# Teensy3_2_v2_peripherie.net
KiCad netlist of a schematic drawn in EAGLE
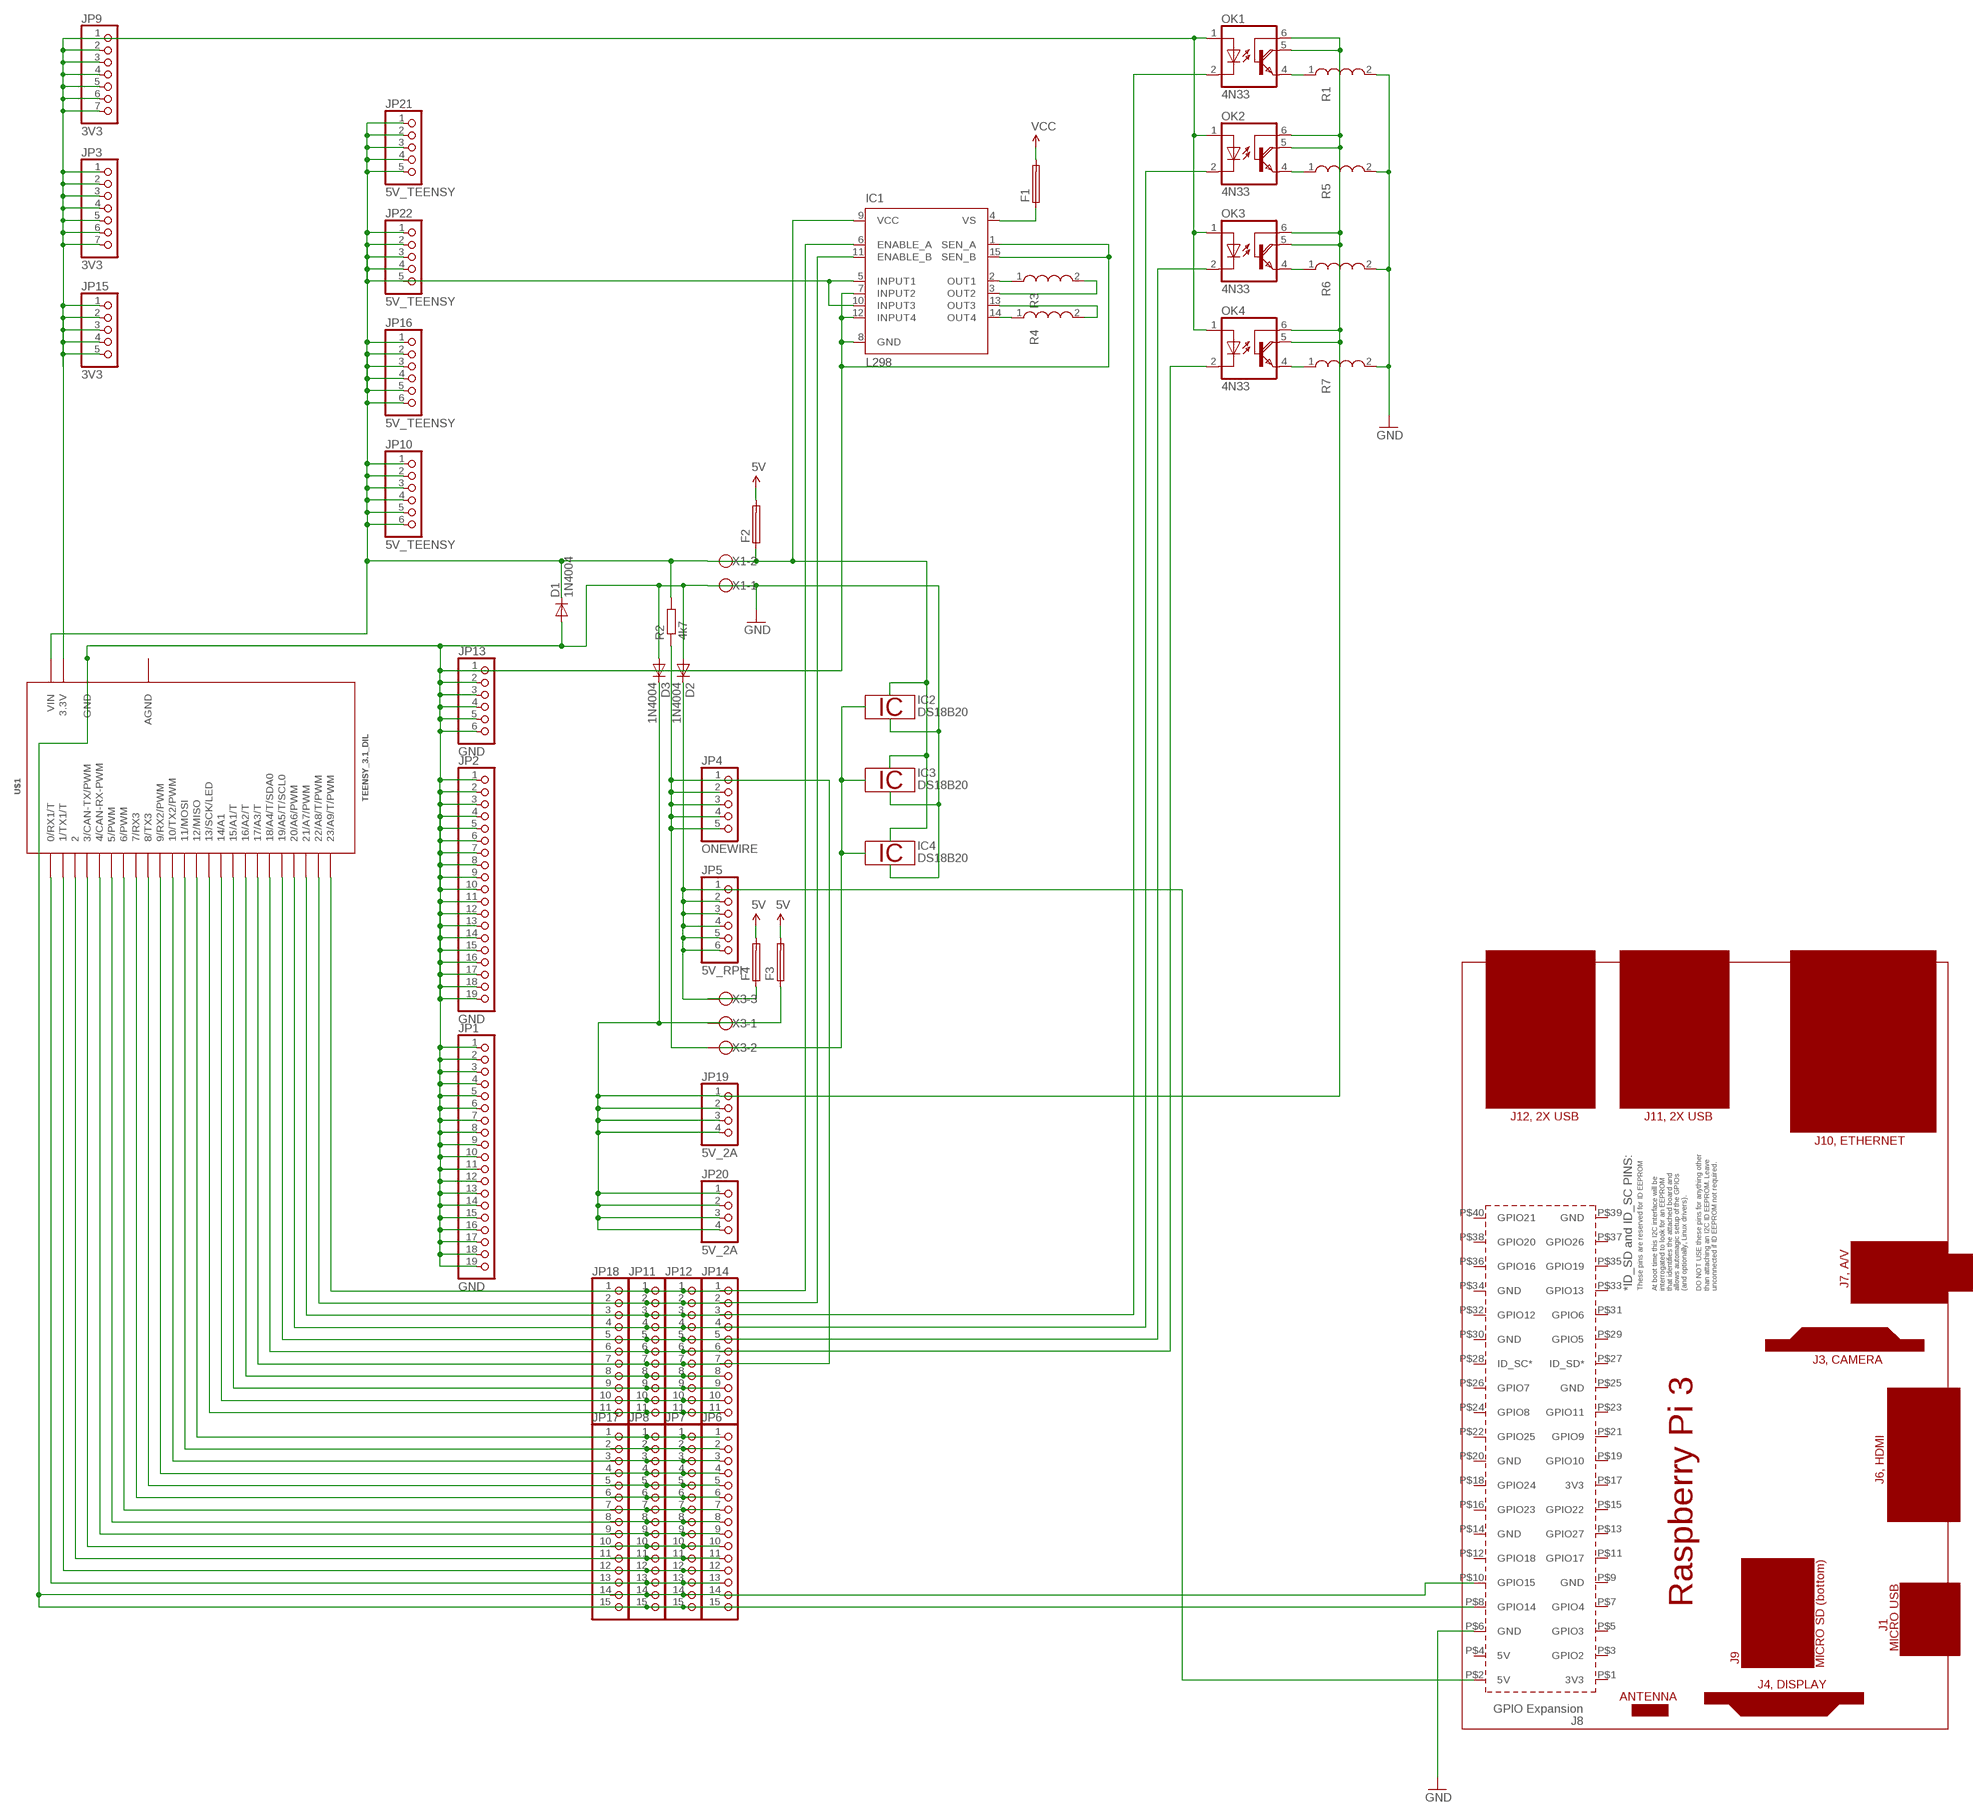
[diagram p0: schematic, sheet 1]

(export (version "E")
  (design (tool "Eeschema 10.0.6"))
  (components
    (comp (ref "D1")
      (value "1N4004")
      (footprint "eagle-import:DO41-10")
      (libsource (lib "eagle-import") (part "1N4004"))
    )
    (comp (ref "D2")
      (value "1N4004")
      (footprint "eagle-import:DO41-10")
      (libsource (lib "eagle-import") (part "1N4004"))
    )
    (comp (ref "D3")
      (value "1N4004")
      (footprint "eagle-import:DO41-10")
      (libsource (lib "eagle-import") (part "1N4004"))
    )
    (comp (ref "F1")
      (value "GSH15")
      (footprint "eagle-import:GSH15")
      (fields (field (name "MPN") "64900001039"))
      (libsource (lib "eagle-import") (part "GSH15"))
    )
    (comp (ref "F2")
      (value "GSH15")
      (footprint "eagle-import:GSH15")
      (fields (field (name "MPN") "64900001039"))
      (libsource (lib "eagle-import") (part "GSH15"))
    )
    (comp (ref "F3")
      (value "GSH15")
      (footprint "eagle-import:GSH15")
      (fields (field (name "MPN") "64900001039"))
      (libsource (lib "eagle-import") (part "GSH15"))
    )
    (comp (ref "F4")
      (value "GSH15")
      (footprint "eagle-import:GSH15")
      (fields (field (name "MPN") "64900001039"))
      (libsource (lib "eagle-import") (part "GSH15"))
    )
    (comp (ref "IC1")
      (value "L298")
      (footprint "eagle-import:MULTIWATT-15")
      (fields (field (name "MPN") "L298N"))
      (libsource (lib "eagle-import") (part "L298"))
    )
    (comp (ref "IC2")
      (value "DS18B20")
      (footprint "eagle-import:TO92-")
      (libsource (lib "eagle-import") (part "DS18B20"))
    )
    (comp (ref "IC3")
      (value "DS18B20")
      (footprint "eagle-import:TO92-")
      (libsource (lib "eagle-import") (part "DS18B20"))
    )
    (comp (ref "IC4")
      (value "DS18B20")
      (footprint "eagle-import:TO92-")
      (libsource (lib "eagle-import") (part "DS18B20"))
    )
    (comp (ref "JP1")
      (value "GND")
      (footprint "eagle-import:1X19")
      (libsource (lib "eagle-import") (part "PINHD-1X19"))
    )
    (comp (ref "JP2")
      (value "GND")
      (footprint "eagle-import:1X19")
      (libsource (lib "eagle-import") (part "PINHD-1X19"))
    )
    (comp (ref "JP3")
      (value "3V3")
      (footprint "eagle-import:1X07")
      (libsource (lib "eagle-import") (part "PINHD-1X7"))
    )
    (comp (ref "JP4")
      (value "ONEWIRE")
      (footprint "eagle-import:1X05")
      (libsource (lib "eagle-import") (part "PINHD-1X5"))
    )
    (comp (ref "JP5")
      (value "5V_RPI")
      (footprint "eagle-import:1X06")
      (libsource (lib "eagle-import") (part "PINHD-1X6"))
    )
    (comp (ref "JP6")
      (value "PINHD-1X15")
      (footprint "eagle-import:1X15")
      (libsource (lib "eagle-import") (part "PINHD-1X15"))
    )
    (comp (ref "JP7")
      (value "PINHD-1X15")
      (footprint "eagle-import:1X15")
      (libsource (lib "eagle-import") (part "PINHD-1X15"))
    )
    (comp (ref "JP8")
      (value "PINHD-1X15")
      (footprint "eagle-import:1X15")
      (libsource (lib "eagle-import") (part "PINHD-1X15"))
    )
    (comp (ref "JP9")
      (value "3V3")
      (footprint "eagle-import:1X07")
      (libsource (lib "eagle-import") (part "PINHD-1X7"))
    )
    (comp (ref "JP10")
      (value "5V_TEENSY")
      (footprint "eagle-import:1X06")
      (libsource (lib "eagle-import") (part "PINHD-1X6"))
    )
    (comp (ref "JP11")
      (value "PINHD-1X11")
      (footprint "eagle-import:1X11")
      (libsource (lib "eagle-import") (part "PINHD-1X11"))
    )
    (comp (ref "JP12")
      (value "PINHD-1X11")
      (footprint "eagle-import:1X11")
      (libsource (lib "eagle-import") (part "PINHD-1X11"))
    )
    (comp (ref "JP13")
      (value "GND")
      (footprint "eagle-import:1X06")
      (libsource (lib "eagle-import") (part "PINHD-1X6"))
    )
    (comp (ref "JP14")
      (value "PINHD-1X11")
      (footprint "eagle-import:1X11")
      (libsource (lib "eagle-import") (part "PINHD-1X11"))
    )
    (comp (ref "JP15")
      (value "3V3")
      (footprint "eagle-import:1X05")
      (libsource (lib "eagle-import") (part "PINHD-1X5"))
    )
    (comp (ref "JP16")
      (value "5V_TEENSY")
      (footprint "eagle-import:1X06")
      (libsource (lib "eagle-import") (part "PINHD-1X6"))
    )
    (comp (ref "JP17")
      (value "PINHD-1X15")
      (footprint "eagle-import:1X15")
      (libsource (lib "eagle-import") (part "PINHD-1X15"))
    )
    (comp (ref "JP18")
      (value "PINHD-1X11")
      (footprint "eagle-import:1X11")
      (libsource (lib "eagle-import") (part "PINHD-1X11"))
    )
    (comp (ref "JP19")
      (value "5V_2A")
      (footprint "eagle-import:1X04")
      (libsource (lib "eagle-import") (part "PINHD-1X4"))
    )
    (comp (ref "JP20")
      (value "5V_2A")
      (footprint "eagle-import:1X04")
      (libsource (lib "eagle-import") (part "PINHD-1X4"))
    )
    (comp (ref "JP21")
      (value "5V_TEENSY")
      (footprint "eagle-import:1X05")
      (libsource (lib "eagle-import") (part "PINHD-1X5"))
    )
    (comp (ref "JP22")
      (value "5V_TEENSY")
      (footprint "eagle-import:1X05")
      (libsource (lib "eagle-import") (part "PINHD-1X5"))
    )
    (comp (ref "OK1")
      (value "4N33")
      (footprint "eagle-import:DIL06")
      (fields (field (name "MF") "VISHAY/TELEFUNKEN"))
      (libsource (lib "eagle-import") (part "4N33"))
    )
    (comp (ref "OK2")
      (value "4N33")
      (footprint "eagle-import:DIL06")
      (fields (field (name "MF") "VISHAY/TELEFUNKEN"))
      (libsource (lib "eagle-import") (part "4N33"))
    )
    (comp (ref "OK3")
      (value "4N33")
      (footprint "eagle-import:DIL06")
      (fields (field (name "MF") "VISHAY/TELEFUNKEN"))
      (libsource (lib "eagle-import") (part "4N33"))
    )
    (comp (ref "OK4")
      (value "4N33")
      (footprint "eagle-import:DIL06")
      (fields (field (name "MF") "VISHAY/TELEFUNKEN"))
      (libsource (lib "eagle-import") (part "4N33"))
    )
    (comp (ref "PCB1")
      (value "RPI3")
      (footprint "eagle-import:RPI3")
      (libsource (lib "eagle-import") (part "RPI3"))
    )
    (comp (ref "R1")
      (value "SPULE_ALTERNATIV")
      (footprint "eagle-import:SPULE")
      (libsource (lib "eagle-import") (part "SPULE_ALTERNATIV"))
    )
    (comp (ref "R2")
      (value "4k7")
      (footprint "eagle-import:0204_5")
      (libsource (lib "eagle-import") (part "R-EU_0204/5"))
    )
    (comp (ref "R3")
      (value "SPULE_ALTERNATIV")
      (footprint "eagle-import:SPULE")
      (libsource (lib "eagle-import") (part "SPULE_ALTERNATIV"))
    )
    (comp (ref "R4")
      (value "SPULE_ALTERNATIV")
      (footprint "eagle-import:SPULE")
      (libsource (lib "eagle-import") (part "SPULE_ALTERNATIV"))
    )
    (comp (ref "R5")
      (value "SPULE_ALTERNATIV")
      (footprint "eagle-import:SPULE")
      (libsource (lib "eagle-import") (part "SPULE_ALTERNATIV"))
    )
    (comp (ref "R6")
      (value "SPULE_ALTERNATIV")
      (footprint "eagle-import:SPULE")
      (libsource (lib "eagle-import") (part "SPULE_ALTERNATIV"))
    )
    (comp (ref "R7")
      (value "SPULE_ALTERNATIV")
      (footprint "eagle-import:SPULE")
      (libsource (lib "eagle-import") (part "SPULE_ALTERNATIV"))
    )
    (comp (ref "U$1")
      (value "TEENSY_3.1_DIL")
      (footprint "eagle-import:TEENSY3-DIL")
      (libsource (lib "eagle-import") (part "TEENSY_3.1_DIL"))
    )
    (comp (ref "X1")
      (value "W237-102")
      (footprint "eagle-import:W237-102")
      (fields (field (name "MPN") "237-102"))
      (libsource (lib "eagle-import") (part "W237-102"))
    )
    (comp (ref "X3")
      (value "W237-103")
      (footprint "eagle-import:W237-103")
      (fields (field (name "MPN") "237-103"))
      (libsource (lib "eagle-import") (part "W237-103"))
    )
  )
  (nets
    (net (code "1") (name "/AGND") (class "Default")
      (node (ref "U$1") (pin "AGND") (pinfunction "AGND_AGND") (pintype "power_in"))
    )
    (net (code "2") (name "5V") (class "Default")
      (node (ref "F2") (pin "2") (pinfunction "2_2") (pintype "passive"))
      (node (ref "F3") (pin "2") (pinfunction "2_2") (pintype "passive"))
      (node (ref "F4") (pin "2") (pinfunction "2_2") (pintype "passive"))
    )
    (net (code "3") (name "GND") (class "Default")
      (node (ref "D1") (pin "A") (pinfunction "A_A") (pintype "passive"))
      (node (ref "D2") (pin "A") (pinfunction "A_A") (pintype "passive"))
      (node (ref "D3") (pin "A") (pinfunction "A_A") (pintype "passive"))
      (node (ref "IC1") (pin "1") (pinfunction "SEN_A_1") (pintype "input"))
      (node (ref "IC1") (pin "12") (pinfunction "INPUT4_12") (pintype "input"))
      (node (ref "IC1") (pin "15") (pinfunction "SEN_B_15") (pintype "input"))
      (node (ref "IC1") (pin "7") (pinfunction "INPUT2_7") (pintype "input"))
      (node (ref "IC1") (pin "8") (pinfunction "GND_8") (pintype "power_in"))
      (node (ref "JP1") (pin "1") (pinfunction "1_1") (pintype "passive"))
      (node (ref "JP1") (pin "10") (pinfunction "10_10") (pintype "passive"))
      (node (ref "JP1") (pin "11") (pinfunction "11_11") (pintype "passive"))
      (node (ref "JP1") (pin "12") (pinfunction "12_12") (pintype "passive"))
      (node (ref "JP1") (pin "13") (pinfunction "13_13") (pintype "passive"))
      (node (ref "JP1") (pin "14") (pinfunction "14_14") (pintype "passive"))
      (node (ref "JP1") (pin "15") (pinfunction "15_15") (pintype "passive"))
      (node (ref "JP1") (pin "16") (pinfunction "16_16") (pintype "passive"))
      (node (ref "JP1") (pin "17") (pinfunction "17_17") (pintype "passive"))
      (node (ref "JP1") (pin "18") (pinfunction "18_18") (pintype "passive"))
      (node (ref "JP1") (pin "19") (pinfunction "19_19") (pintype "passive"))
      (node (ref "JP1") (pin "2") (pinfunction "2_2") (pintype "passive"))
      (node (ref "JP1") (pin "3") (pinfunction "3_3") (pintype "passive"))
      (node (ref "JP1") (pin "4") (pinfunction "4_4") (pintype "passive"))
      (node (ref "JP1") (pin "5") (pinfunction "5_5") (pintype "passive"))
      (node (ref "JP1") (pin "6") (pinfunction "6_6") (pintype "passive"))
      (node (ref "JP1") (pin "7") (pinfunction "7_7") (pintype "passive"))
      (node (ref "JP1") (pin "8") (pinfunction "8_8") (pintype "passive"))
      (node (ref "JP1") (pin "9") (pinfunction "9_9") (pintype "passive"))
      (node (ref "JP13") (pin "1") (pinfunction "1_1") (pintype "passive"))
      (node (ref "JP13") (pin "2") (pinfunction "2_2") (pintype "passive"))
      (node (ref "JP13") (pin "3") (pinfunction "3_3") (pintype "passive"))
      (node (ref "JP13") (pin "4") (pinfunction "4_4") (pintype "passive"))
      (node (ref "JP13") (pin "5") (pinfunction "5_5") (pintype "passive"))
      (node (ref "JP13") (pin "6") (pinfunction "6_6") (pintype "passive"))
      (node (ref "JP17") (pin "14") (pinfunction "14_14") (pintype "passive"))
      (node (ref "JP17") (pin "15") (pinfunction "15_15") (pintype "passive"))
      (node (ref "JP2") (pin "1") (pinfunction "1_1") (pintype "passive"))
      (node (ref "JP2") (pin "10") (pinfunction "10_10") (pintype "passive"))
      (node (ref "JP2") (pin "11") (pinfunction "11_11") (pintype "passive"))
      (node (ref "JP2") (pin "12") (pinfunction "12_12") (pintype "passive"))
      (node (ref "JP2") (pin "13") (pinfunction "13_13") (pintype "passive"))
      (node (ref "JP2") (pin "14") (pinfunction "14_14") (pintype "passive"))
      (node (ref "JP2") (pin "15") (pinfunction "15_15") (pintype "passive"))
      (node (ref "JP2") (pin "16") (pinfunction "16_16") (pintype "passive"))
      (node (ref "JP2") (pin "17") (pinfunction "17_17") (pintype "passive"))
      (node (ref "JP2") (pin "18") (pinfunction "18_18") (pintype "passive"))
      (node (ref "JP2") (pin "19") (pinfunction "19_19") (pintype "passive"))
      (node (ref "JP2") (pin "2") (pinfunction "2_2") (pintype "passive"))
      (node (ref "JP2") (pin "3") (pinfunction "3_3") (pintype "passive"))
      (node (ref "JP2") (pin "4") (pinfunction "4_4") (pintype "passive"))
      (node (ref "JP2") (pin "5") (pinfunction "5_5") (pintype "passive"))
      (node (ref "JP2") (pin "6") (pinfunction "6_6") (pintype "passive"))
      (node (ref "JP2") (pin "7") (pinfunction "7_7") (pintype "passive"))
      (node (ref "JP2") (pin "8") (pinfunction "8_8") (pintype "passive"))
      (node (ref "JP2") (pin "9") (pinfunction "9_9") (pintype "passive"))
      (node (ref "JP6") (pin "14") (pinfunction "14_14") (pintype "passive"))
      (node (ref "JP6") (pin "15") (pinfunction "15_15") (pintype "passive"))
      (node (ref "JP7") (pin "14") (pinfunction "14_14") (pintype "passive"))
      (node (ref "JP7") (pin "15") (pinfunction "15_15") (pintype "passive"))
      (node (ref "JP8") (pin "14") (pinfunction "14_14") (pintype "passive"))
      (node (ref "JP8") (pin "15") (pinfunction "15_15") (pintype "passive"))
      (node (ref "PCB1") (pin "P$10") (pinfunction "GPIO15_P$10") (pintype "bidirectional"))
      (node (ref "PCB1") (pin "P$6") (pinfunction "GND_P$6") (pintype "bidirectional"))
      (node (ref "PCB1") (pin "P$8") (pinfunction "GPIO14_P$8") (pintype "bidirectional"))
      (node (ref "R1") (pin "2") (pinfunction "2_2") (pintype "passive"))
      (node (ref "R5") (pin "2") (pinfunction "2_2") (pintype "passive"))
      (node (ref "R6") (pin "2") (pinfunction "2_2") (pintype "passive"))
      (node (ref "R7") (pin "2") (pinfunction "2_2") (pintype "passive"))
      (node (ref "U$1") (pin "GND") (pinfunction "GND_GND") (pintype "power_in"))
      (node (ref "X1") (pin "1") (pinfunction "KL_1") (pintype "passive"))
    )
    (net (code "4") (name "Net-(IC1-ENABLE_A)") (class "Default")
      (node (ref "IC1") (pin "6") (pinfunction "ENABLE_A_6") (pintype "input"))
      (node (ref "JP11") (pin "1") (pinfunction "1_1") (pintype "passive"))
      (node (ref "JP12") (pin "1") (pinfunction "1_1") (pintype "passive"))
      (node (ref "JP14") (pin "1") (pinfunction "1_1") (pintype "passive"))
      (node (ref "JP18") (pin "1") (pinfunction "1_1") (pintype "passive"))
      (node (ref "U$1") (pin "23/A9") (pinfunction "23/A9/T/PWM_23/A9") (pintype "bidirectional"))
    )
    (net (code "5") (name "Net-(IC1-ENABLE_B)") (class "Default")
      (node (ref "IC1") (pin "11") (pinfunction "ENABLE_B_11") (pintype "input"))
      (node (ref "JP11") (pin "2") (pinfunction "2_2") (pintype "passive"))
      (node (ref "JP12") (pin "2") (pinfunction "2_2") (pintype "passive"))
      (node (ref "JP14") (pin "2") (pinfunction "2_2") (pintype "passive"))
      (node (ref "JP18") (pin "2") (pinfunction "2_2") (pintype "passive"))
      (node (ref "U$1") (pin "22/A8") (pinfunction "22/A8/T/PWM_22/A8") (pintype "bidirectional"))
    )
    (net (code "6") (name "Net-(IC1-INPUT1)") (class "Default")
      (node (ref "D1") (pin "C") (pinfunction "C_C") (pintype "passive"))
      (node (ref "F2") (pin "1") (pinfunction "1_1") (pintype "passive"))
      (node (ref "IC1") (pin "10") (pinfunction "INPUT3_10") (pintype "input"))
      (node (ref "IC1") (pin "5") (pinfunction "INPUT1_5") (pintype "input"))
      (node (ref "IC1") (pin "9") (pinfunction "VCC_9") (pintype "power_in"))
      (node (ref "JP10") (pin "1") (pinfunction "1_1") (pintype "passive"))
      (node (ref "JP10") (pin "2") (pinfunction "2_2") (pintype "passive"))
      (node (ref "JP10") (pin "3") (pinfunction "3_3") (pintype "passive"))
      (node (ref "JP10") (pin "4") (pinfunction "4_4") (pintype "passive"))
      (node (ref "JP10") (pin "5") (pinfunction "5_5") (pintype "passive"))
      (node (ref "JP10") (pin "6") (pinfunction "6_6") (pintype "passive"))
      (node (ref "JP16") (pin "1") (pinfunction "1_1") (pintype "passive"))
      (node (ref "JP16") (pin "2") (pinfunction "2_2") (pintype "passive"))
      (node (ref "JP16") (pin "3") (pinfunction "3_3") (pintype "passive"))
      (node (ref "JP16") (pin "4") (pinfunction "4_4") (pintype "passive"))
      (node (ref "JP16") (pin "5") (pinfunction "5_5") (pintype "passive"))
      (node (ref "JP16") (pin "6") (pinfunction "6_6") (pintype "passive"))
      (node (ref "JP21") (pin "1") (pinfunction "1_1") (pintype "passive"))
      (node (ref "JP21") (pin "2") (pinfunction "2_2") (pintype "passive"))
      (node (ref "JP21") (pin "3") (pinfunction "3_3") (pintype "passive"))
      (node (ref "JP21") (pin "4") (pinfunction "4_4") (pintype "passive"))
      (node (ref "JP21") (pin "5") (pinfunction "5_5") (pintype "passive"))
      (node (ref "JP22") (pin "1") (pinfunction "1_1") (pintype "passive"))
      (node (ref "JP22") (pin "2") (pinfunction "2_2") (pintype "passive"))
      (node (ref "JP22") (pin "3") (pinfunction "3_3") (pintype "passive"))
      (node (ref "JP22") (pin "4") (pinfunction "4_4") (pintype "passive"))
      (node (ref "JP22") (pin "5") (pinfunction "5_5") (pintype "passive"))
      (node (ref "R2") (pin "2") (pinfunction "2_2") (pintype "passive"))
      (node (ref "U$1") (pin "VIN") (pinfunction "VIN_VIN") (pintype "power_in"))
      (node (ref "X1") (pin "2") (pinfunction "KL_2") (pintype "passive"))
    )
    (net (code "7") (name "Net-(IC1-OUT1)") (class "Default")
      (node (ref "IC1") (pin "2") (pinfunction "OUT1_2") (pintype "output"))
      (node (ref "R3") (pin "1") (pinfunction "1_1") (pintype "passive"))
    )
    (net (code "8") (name "Net-(IC1-OUT2)") (class "Default")
      (node (ref "IC1") (pin "3") (pinfunction "OUT2_3") (pintype "output"))
      (node (ref "R3") (pin "2") (pinfunction "2_2") (pintype "passive"))
    )
    (net (code "9") (name "Net-(IC1-OUT3)") (class "Default")
      (node (ref "IC1") (pin "13") (pinfunction "OUT3_13") (pintype "output"))
      (node (ref "R4") (pin "2") (pinfunction "2_2") (pintype "passive"))
    )
    (net (code "10") (name "Net-(IC1-OUT4)") (class "Default")
      (node (ref "IC1") (pin "14") (pinfunction "OUT4_14") (pintype "output"))
      (node (ref "R4") (pin "1") (pinfunction "1_1") (pintype "passive"))
    )
    (net (code "11") (name "Net-(IC1-VS)") (class "Default")
      (node (ref "F1") (pin "1") (pinfunction "1_1") (pintype "passive"))
      (node (ref "IC1") (pin "4") (pinfunction "VS_4") (pintype "power_in"))
    )
    (net (code "12") (name "Net-(JP17-Pad11)") (class "Default")
      (node (ref "JP17") (pin "11") (pinfunction "11_11") (pintype "passive"))
      (node (ref "JP6") (pin "11") (pinfunction "11_11") (pintype "passive"))
      (node (ref "JP7") (pin "11") (pinfunction "11_11") (pintype "passive"))
      (node (ref "JP8") (pin "11") (pinfunction "11_11") (pintype "passive"))
      (node (ref "U$1") (pin "2") (pinfunction "2_2") (pintype "bidirectional"))
    )
    (net (code "13") (name "Net-(OK1-A)") (class "Default")
      (node (ref "JP15") (pin "1") (pinfunction "1_1") (pintype "passive"))
      (node (ref "JP15") (pin "2") (pinfunction "2_2") (pintype "passive"))
      (node (ref "JP15") (pin "3") (pinfunction "3_3") (pintype "passive"))
      (node (ref "JP15") (pin "4") (pinfunction "4_4") (pintype "passive"))
      (node (ref "JP15") (pin "5") (pinfunction "5_5") (pintype "passive"))
      (node (ref "JP3") (pin "1") (pinfunction "1_1") (pintype "passive"))
      (node (ref "JP3") (pin "2") (pinfunction "2_2") (pintype "passive"))
      (node (ref "JP3") (pin "3") (pinfunction "3_3") (pintype "passive"))
      (node (ref "JP3") (pin "4") (pinfunction "4_4") (pintype "passive"))
      (node (ref "JP3") (pin "5") (pinfunction "5_5") (pintype "passive"))
      (node (ref "JP3") (pin "6") (pinfunction "6_6") (pintype "passive"))
      (node (ref "JP3") (pin "7") (pinfunction "7_7") (pintype "passive"))
      (node (ref "JP9") (pin "1") (pinfunction "1_1") (pintype "passive"))
      (node (ref "JP9") (pin "2") (pinfunction "2_2") (pintype "passive"))
      (node (ref "JP9") (pin "3") (pinfunction "3_3") (pintype "passive"))
      (node (ref "JP9") (pin "4") (pinfunction "4_4") (pintype "passive"))
      (node (ref "JP9") (pin "5") (pinfunction "5_5") (pintype "passive"))
      (node (ref "JP9") (pin "6") (pinfunction "6_6") (pintype "passive"))
      (node (ref "JP9") (pin "7") (pinfunction "7_7") (pintype "passive"))
      (node (ref "OK1") (pin "1") (pinfunction "A_1") (pintype "passive"))
      (node (ref "OK2") (pin "1") (pinfunction "A_1") (pintype "passive"))
      (node (ref "OK3") (pin "1") (pinfunction "A_1") (pintype "passive"))
      (node (ref "OK4") (pin "1") (pinfunction "A_1") (pintype "passive"))
      (node (ref "U$1") (pin "3.3V") (pinfunction "3.3V_3.3V") (pintype "power_in"))
    )
    (net (code "14") (name "Net-(OK1-B)") (class "Default")
      (node (ref "D3") (pin "C") (pinfunction "C_C") (pintype "passive"))
      (node (ref "F3") (pin "1") (pinfunction "1_1") (pintype "passive"))
      (node (ref "JP19") (pin "1") (pinfunction "1_1") (pintype "passive"))
      (node (ref "JP19") (pin "2") (pinfunction "2_2") (pintype "passive"))
      (node (ref "JP19") (pin "3") (pinfunction "3_3") (pintype "passive"))
      (node (ref "JP19") (pin "4") (pinfunction "4_4") (pintype "passive"))
      (node (ref "JP20") (pin "1") (pinfunction "1_1") (pintype "passive"))
      (node (ref "JP20") (pin "2") (pinfunction "2_2") (pintype "passive"))
      (node (ref "JP20") (pin "3") (pinfunction "3_3") (pintype "passive"))
      (node (ref "JP20") (pin "4") (pinfunction "4_4") (pintype "passive"))
      (node (ref "OK1") (pin "5") (pinfunction "COL_5") (pintype "passive"))
      (node (ref "OK1") (pin "6") (pinfunction "B_6") (pintype "passive"))
      (node (ref "OK2") (pin "5") (pinfunction "COL_5") (pintype "passive"))
      (node (ref "OK2") (pin "6") (pinfunction "B_6") (pintype "passive"))
      (node (ref "OK3") (pin "5") (pinfunction "COL_5") (pintype "passive"))
      (node (ref "OK3") (pin "6") (pinfunction "B_6") (pintype "passive"))
      (node (ref "OK4") (pin "5") (pinfunction "COL_5") (pintype "passive"))
      (node (ref "OK4") (pin "6") (pinfunction "B_6") (pintype "passive"))
      (node (ref "X3") (pin "1") (pinfunction "KL_1") (pintype "passive"))
    )
    (net (code "15") (name "Net-(OK1-C)") (class "Default")
      (node (ref "JP11") (pin "3") (pinfunction "3_3") (pintype "passive"))
      (node (ref "JP12") (pin "3") (pinfunction "3_3") (pintype "passive"))
      (node (ref "JP14") (pin "3") (pinfunction "3_3") (pintype "passive"))
      (node (ref "JP18") (pin "3") (pinfunction "3_3") (pintype "passive"))
      (node (ref "OK1") (pin "2") (pinfunction "C_2") (pintype "passive"))
      (node (ref "U$1") (pin "21/A7") (pinfunction "21/A7/PWM_21/A7") (pintype "bidirectional"))
    )
    (net (code "16") (name "Net-(OK1-E)") (class "Default")
      (node (ref "OK1") (pin "4") (pinfunction "E_4") (pintype "passive"))
      (node (ref "R1") (pin "1") (pinfunction "1_1") (pintype "passive"))
    )
    (net (code "17") (name "Net-(OK2-C)") (class "Default")
      (node (ref "JP11") (pin "4") (pinfunction "4_4") (pintype "passive"))
      (node (ref "JP12") (pin "4") (pinfunction "4_4") (pintype "passive"))
      (node (ref "JP14") (pin "4") (pinfunction "4_4") (pintype "passive"))
      (node (ref "JP18") (pin "4") (pinfunction "4_4") (pintype "passive"))
      (node (ref "OK2") (pin "2") (pinfunction "C_2") (pintype "passive"))
      (node (ref "U$1") (pin "20/A6") (pinfunction "20/A6/PWM_20/A6") (pintype "bidirectional"))
    )
    (net (code "18") (name "Net-(OK2-E)") (class "Default")
      (node (ref "OK2") (pin "4") (pinfunction "E_4") (pintype "passive"))
      (node (ref "R5") (pin "1") (pinfunction "1_1") (pintype "passive"))
    )
    (net (code "19") (name "Net-(OK3-C)") (class "Default")
      (node (ref "JP11") (pin "5") (pinfunction "5_5") (pintype "passive"))
      (node (ref "JP12") (pin "5") (pinfunction "5_5") (pintype "passive"))
      (node (ref "JP14") (pin "5") (pinfunction "5_5") (pintype "passive"))
      (node (ref "JP18") (pin "5") (pinfunction "5_5") (pintype "passive"))
      (node (ref "OK3") (pin "2") (pinfunction "C_2") (pintype "passive"))
      (node (ref "U$1") (pin "19/A5") (pinfunction "19/A5/T/SCL0_19/A5") (pintype "bidirectional"))
    )
    (net (code "20") (name "Net-(OK3-E)") (class "Default")
      (node (ref "OK3") (pin "4") (pinfunction "E_4") (pintype "passive"))
      (node (ref "R6") (pin "1") (pinfunction "1_1") (pintype "passive"))
    )
    (net (code "21") (name "Net-(OK4-C)") (class "Default")
      (node (ref "JP11") (pin "6") (pinfunction "6_6") (pintype "passive"))
      (node (ref "JP12") (pin "6") (pinfunction "6_6") (pintype "passive"))
      (node (ref "JP14") (pin "6") (pinfunction "6_6") (pintype "passive"))
      (node (ref "JP18") (pin "6") (pinfunction "6_6") (pintype "passive"))
      (node (ref "OK4") (pin "2") (pinfunction "C_2") (pintype "passive"))
      (node (ref "U$1") (pin "18/A4") (pinfunction "18/A4/T/SDA0_18/A4") (pintype "bidirectional"))
    )
    (net (code "22") (name "Net-(OK4-E)") (class "Default")
      (node (ref "OK4") (pin "4") (pinfunction "E_4") (pintype "passive"))
      (node (ref "R7") (pin "1") (pinfunction "1_1") (pintype "passive"))
    )
    (net (code "23") (name "Net-(U$1-0{slash}RX1{slash}T)") (class "Default")
      (node (ref "JP17") (pin "13") (pinfunction "13_13") (pintype "passive"))
      (node (ref "JP6") (pin "13") (pinfunction "13_13") (pintype "passive"))
      (node (ref "JP7") (pin "13") (pinfunction "13_13") (pintype "passive"))
      (node (ref "JP8") (pin "13") (pinfunction "13_13") (pintype "passive"))
      (node (ref "U$1") (pin "0") (pinfunction "0/RX1/T_0") (pintype "bidirectional"))
    )
    (net (code "24") (name "Net-(U$1-1{slash}TX1{slash}T)") (class "Default")
      (node (ref "JP17") (pin "12") (pinfunction "12_12") (pintype "passive"))
      (node (ref "JP6") (pin "12") (pinfunction "12_12") (pintype "passive"))
      (node (ref "JP7") (pin "12") (pinfunction "12_12") (pintype "passive"))
      (node (ref "JP8") (pin "12") (pinfunction "12_12") (pintype "passive"))
      (node (ref "U$1") (pin "1") (pinfunction "1/TX1/T_1") (pintype "bidirectional"))
    )
    (net (code "25") (name "Net-(U$1-3{slash}CAN-TX{slash}PWM)") (class "Default")
      (node (ref "JP17") (pin "10") (pinfunction "10_10") (pintype "passive"))
      (node (ref "JP6") (pin "10") (pinfunction "10_10") (pintype "passive"))
      (node (ref "JP7") (pin "10") (pinfunction "10_10") (pintype "passive"))
      (node (ref "JP8") (pin "10") (pinfunction "10_10") (pintype "passive"))
      (node (ref "U$1") (pin "3") (pinfunction "3/CAN-TX/PWM_3") (pintype "bidirectional"))
    )
    (net (code "26") (name "Net-(U$1-4{slash}CAN-RX-PWM)") (class "Default")
      (node (ref "JP17") (pin "9") (pinfunction "9_9") (pintype "passive"))
      (node (ref "JP6") (pin "9") (pinfunction "9_9") (pintype "passive"))
      (node (ref "JP7") (pin "9") (pinfunction "9_9") (pintype "passive"))
      (node (ref "JP8") (pin "9") (pinfunction "9_9") (pintype "passive"))
      (node (ref "U$1") (pin "4") (pinfunction "4/CAN-RX-PWM_4") (pintype "bidirectional"))
    )
    (net (code "27") (name "Net-(U$1-5{slash}PWM)") (class "Default")
      (node (ref "JP17") (pin "8") (pinfunction "8_8") (pintype "passive"))
      (node (ref "JP6") (pin "8") (pinfunction "8_8") (pintype "passive"))
      (node (ref "JP7") (pin "8") (pinfunction "8_8") (pintype "passive"))
      (node (ref "JP8") (pin "8") (pinfunction "8_8") (pintype "passive"))
      (node (ref "U$1") (pin "5") (pinfunction "5/PWM_5") (pintype "bidirectional"))
    )
    (net (code "28") (name "Net-(U$1-6{slash}PWM)") (class "Default")
      (node (ref "JP17") (pin "7") (pinfunction "7_7") (pintype "passive"))
      (node (ref "JP6") (pin "7") (pinfunction "7_7") (pintype "passive"))
      (node (ref "JP7") (pin "7") (pinfunction "7_7") (pintype "passive"))
      (node (ref "JP8") (pin "7") (pinfunction "7_7") (pintype "passive"))
      (node (ref "U$1") (pin "6") (pinfunction "6/PWM_6") (pintype "bidirectional"))
    )
    (net (code "29") (name "Net-(U$1-7{slash}RX3)") (class "Default")
      (node (ref "JP17") (pin "6") (pinfunction "6_6") (pintype "passive"))
      (node (ref "JP6") (pin "6") (pinfunction "6_6") (pintype "passive"))
      (node (ref "JP7") (pin "6") (pinfunction "6_6") (pintype "passive"))
      (node (ref "JP8") (pin "6") (pinfunction "6_6") (pintype "passive"))
      (node (ref "U$1") (pin "7") (pinfunction "7/RX3_7") (pintype "bidirectional"))
    )
    (net (code "30") (name "Net-(U$1-8{slash}TX3)") (class "Default")
      (node (ref "JP17") (pin "5") (pinfunction "5_5") (pintype "passive"))
      (node (ref "JP6") (pin "5") (pinfunction "5_5") (pintype "passive"))
      (node (ref "JP7") (pin "5") (pinfunction "5_5") (pintype "passive"))
      (node (ref "JP8") (pin "5") (pinfunction "5_5") (pintype "passive"))
      (node (ref "U$1") (pin "8") (pinfunction "8/TX3_8") (pintype "bidirectional"))
    )
    (net (code "31") (name "Net-(U$1-9{slash}RX2{slash}PWM)") (class "Default")
      (node (ref "JP17") (pin "4") (pinfunction "4_4") (pintype "passive"))
      (node (ref "JP6") (pin "4") (pinfunction "4_4") (pintype "passive"))
      (node (ref "JP7") (pin "4") (pinfunction "4_4") (pintype "passive"))
      (node (ref "JP8") (pin "4") (pinfunction "4_4") (pintype "passive"))
      (node (ref "U$1") (pin "9") (pinfunction "9/RX2/PWM_9") (pintype "bidirectional"))
    )
    (net (code "32") (name "Net-(U$1-10{slash}TX2{slash}PWM)") (class "Default")
      (node (ref "JP17") (pin "3") (pinfunction "3_3") (pintype "passive"))
      (node (ref "JP6") (pin "3") (pinfunction "3_3") (pintype "passive"))
      (node (ref "JP7") (pin "3") (pinfunction "3_3") (pintype "passive"))
      (node (ref "JP8") (pin "3") (pinfunction "3_3") (pintype "passive"))
      (node (ref "U$1") (pin "10") (pinfunction "10/TX2/PWM_10") (pintype "bidirectional"))
    )
    (net (code "33") (name "Net-(U$1-11{slash}MOSI)") (class "Default")
      (node (ref "JP17") (pin "2") (pinfunction "2_2") (pintype "passive"))
      (node (ref "JP6") (pin "2") (pinfunction "2_2") (pintype "passive"))
      (node (ref "JP7") (pin "2") (pinfunction "2_2") (pintype "passive"))
      (node (ref "JP8") (pin "2") (pinfunction "2_2") (pintype "passive"))
      (node (ref "U$1") (pin "11") (pinfunction "11/MOSI_11") (pintype "bidirectional"))
    )
    (net (code "34") (name "Net-(U$1-12{slash}MISO)") (class "Default")
      (node (ref "JP17") (pin "1") (pinfunction "1_1") (pintype "passive"))
      (node (ref "JP6") (pin "1") (pinfunction "1_1") (pintype "passive"))
      (node (ref "JP7") (pin "1") (pinfunction "1_1") (pintype "passive"))
      (node (ref "JP8") (pin "1") (pinfunction "1_1") (pintype "passive"))
      (node (ref "U$1") (pin "12") (pinfunction "12/MISO_12") (pintype "bidirectional"))
    )
    (net (code "35") (name "Net-(U$1-13{slash}SCK{slash}LED)") (class "Default")
      (node (ref "JP11") (pin "11") (pinfunction "11_11") (pintype "passive"))
      (node (ref "JP12") (pin "11") (pinfunction "11_11") (pintype "passive"))
      (node (ref "JP14") (pin "11") (pinfunction "11_11") (pintype "passive"))
      (node (ref "JP18") (pin "11") (pinfunction "11_11") (pintype "passive"))
      (node (ref "U$1") (pin "13") (pinfunction "13/SCK/LED_13") (pintype "bidirectional"))
    )
    (net (code "36") (name "Net-(U$1-14{slash}A1)") (class "Default")
      (node (ref "JP11") (pin "10") (pinfunction "10_10") (pintype "passive"))
      (node (ref "JP12") (pin "10") (pinfunction "10_10") (pintype "passive"))
      (node (ref "JP14") (pin "10") (pinfunction "10_10") (pintype "passive"))
      (node (ref "JP18") (pin "10") (pinfunction "10_10") (pintype "passive"))
      (node (ref "U$1") (pin "14/A0") (pinfunction "14/A1_14/A0") (pintype "bidirectional"))
    )
    (net (code "37") (name "Net-(U$1-15{slash}A1{slash}T)") (class "Default")
      (node (ref "JP11") (pin "9") (pinfunction "9_9") (pintype "passive"))
      (node (ref "JP12") (pin "9") (pinfunction "9_9") (pintype "passive"))
      (node (ref "JP14") (pin "9") (pinfunction "9_9") (pintype "passive"))
      (node (ref "JP18") (pin "9") (pinfunction "9_9") (pintype "passive"))
      (node (ref "U$1") (pin "15/A1") (pinfunction "15/A1/T_15/A1") (pintype "bidirectional"))
    )
    (net (code "38") (name "Net-(U$1-16{slash}A2{slash}T)") (class "Default")
      (node (ref "JP11") (pin "8") (pinfunction "8_8") (pintype "passive"))
      (node (ref "JP12") (pin "8") (pinfunction "8_8") (pintype "passive"))
      (node (ref "JP14") (pin "8") (pinfunction "8_8") (pintype "passive"))
      (node (ref "JP18") (pin "8") (pinfunction "8_8") (pintype "passive"))
      (node (ref "U$1") (pin "16/A2") (pinfunction "16/A2/T_16/A2") (pintype "bidirectional"))
    )
    (net (code "39") (name "Net-(U$1-17{slash}A3{slash}T)") (class "Default")
      (node (ref "JP11") (pin "7") (pinfunction "7_7") (pintype "passive"))
      (node (ref "JP12") (pin "7") (pinfunction "7_7") (pintype "passive"))
      (node (ref "JP14") (pin "7") (pinfunction "7_7") (pintype "passive"))
      (node (ref "JP18") (pin "7") (pinfunction "7_7") (pintype "passive"))
      (node (ref "JP4") (pin "1") (pinfunction "1_1") (pintype "passive"))
      (node (ref "JP4") (pin "2") (pinfunction "2_2") (pintype "passive"))
      (node (ref "JP4") (pin "3") (pinfunction "3_3") (pintype "passive"))
      (node (ref "JP4") (pin "4") (pinfunction "4_4") (pintype "passive"))
      (node (ref "JP4") (pin "5") (pinfunction "5_5") (pintype "passive"))
      (node (ref "R2") (pin "1") (pinfunction "1_1") (pintype "passive"))
      (node (ref "U$1") (pin "17/A3") (pinfunction "17/A3/T_17/A3") (pintype "bidirectional"))
      (node (ref "X3") (pin "2") (pinfunction "KL_2") (pintype "passive"))
    )
    (net (code "40") (name "Net-(X3C-KL)") (class "Default")
      (node (ref "D2") (pin "C") (pinfunction "C_C") (pintype "passive"))
      (node (ref "F4") (pin "1") (pinfunction "1_1") (pintype "passive"))
      (node (ref "JP5") (pin "1") (pinfunction "1_1") (pintype "passive"))
      (node (ref "JP5") (pin "2") (pinfunction "2_2") (pintype "passive"))
      (node (ref "JP5") (pin "3") (pinfunction "3_3") (pintype "passive"))
      (node (ref "JP5") (pin "4") (pinfunction "4_4") (pintype "passive"))
      (node (ref "JP5") (pin "5") (pinfunction "5_5") (pintype "passive"))
      (node (ref "JP5") (pin "6") (pinfunction "6_6") (pintype "passive"))
      (node (ref "PCB1") (pin "P$2") (pinfunction "5V_P$2") (pintype "bidirectional"))
      (node (ref "X3") (pin "3") (pinfunction "KL_3") (pintype "passive"))
    )
    (net (code "41") (name "VCC") (class "Default")
      (node (ref "F1") (pin "2") (pinfunction "2_2") (pintype "passive"))
    )
    (net (code "42") (name "unconnected-(PCB1-3V3-PadP$1)") (class "Default")
      (node (ref "PCB1") (pin "P$1") (pinfunction "3V3_P$1") (pintype "bidirectional"))
    )
    (net (code "43") (name "unconnected-(PCB1-3V3-PadP$17)") (class "Default")
      (node (ref "PCB1") (pin "P$17") (pinfunction "3V3_P$17") (pintype "bidirectional"))
    )
    (net (code "44") (name "unconnected-(PCB1-5V-PadP$4)") (class "Default")
      (node (ref "PCB1") (pin "P$4") (pinfunction "5V_P$4") (pintype "bidirectional"))
    )
    (net (code "45") (name "unconnected-(PCB1-GND-PadP$9)") (class "Default")
      (node (ref "PCB1") (pin "P$9") (pinfunction "GND_P$9") (pintype "bidirectional"))
    )
    (net (code "46") (name "unconnected-(PCB1-GND-PadP$14)") (class "Default")
      (node (ref "PCB1") (pin "P$14") (pinfunction "GND_P$14") (pintype "bidirectional"))
    )
    (net (code "47") (name "unconnected-(PCB1-GND-PadP$20)") (class "Default")
      (node (ref "PCB1") (pin "P$20") (pinfunction "GND_P$20") (pintype "bidirectional"))
    )
    (net (code "48") (name "unconnected-(PCB1-GND-PadP$25)") (class "Default")
      (node (ref "PCB1") (pin "P$25") (pinfunction "GND_P$25") (pintype "bidirectional"))
    )
    (net (code "49") (name "unconnected-(PCB1-GND-PadP$30)") (class "Default")
      (node (ref "PCB1") (pin "P$30") (pinfunction "GND_P$30") (pintype "bidirectional"))
    )
    (net (code "50") (name "unconnected-(PCB1-GND-PadP$34)") (class "Default")
      (node (ref "PCB1") (pin "P$34") (pinfunction "GND_P$34") (pintype "bidirectional"))
    )
    (net (code "51") (name "unconnected-(PCB1-GND-PadP$39)") (class "Default")
      (node (ref "PCB1") (pin "P$39") (pinfunction "GND_P$39") (pintype "bidirectional"))
    )
    (net (code "52") (name "unconnected-(PCB1-GPIO2-PadP$3)") (class "Default")
      (node (ref "PCB1") (pin "P$3") (pinfunction "GPIO2_P$3") (pintype "bidirectional"))
    )
    (net (code "53") (name "unconnected-(PCB1-GPIO3-PadP$5)") (class "Default")
      (node (ref "PCB1") (pin "P$5") (pinfunction "GPIO3_P$5") (pintype "bidirectional"))
    )
    (net (code "54") (name "unconnected-(PCB1-GPIO4-PadP$7)") (class "Default")
      (node (ref "PCB1") (pin "P$7") (pinfunction "GPIO4_P$7") (pintype "bidirectional"))
    )
    (net (code "55") (name "unconnected-(PCB1-GPIO5-PadP$29)") (class "Default")
      (node (ref "PCB1") (pin "P$29") (pinfunction "GPIO5_P$29") (pintype "bidirectional"))
    )
    (net (code "56") (name "unconnected-(PCB1-GPIO6-PadP$31)") (class "Default")
      (node (ref "PCB1") (pin "P$31") (pinfunction "GPIO6_P$31") (pintype "bidirectional"))
    )
    (net (code "57") (name "unconnected-(PCB1-GPIO7-PadP$26)") (class "Default")
      (node (ref "PCB1") (pin "P$26") (pinfunction "GPIO7_P$26") (pintype "bidirectional"))
    )
    (net (code "58") (name "unconnected-(PCB1-GPIO8-PadP$24)") (class "Default")
      (node (ref "PCB1") (pin "P$24") (pinfunction "GPIO8_P$24") (pintype "bidirectional"))
    )
    (net (code "59") (name "unconnected-(PCB1-GPIO9-PadP$21)") (class "Default")
      (node (ref "PCB1") (pin "P$21") (pinfunction "GPIO9_P$21") (pintype "bidirectional"))
    )
    (net (code "60") (name "unconnected-(PCB1-GPIO10-PadP$19)") (class "Default")
      (node (ref "PCB1") (pin "P$19") (pinfunction "GPIO10_P$19") (pintype "bidirectional"))
    )
    (net (code "61") (name "unconnected-(PCB1-GPIO11-PadP$23)") (class "Default")
      (node (ref "PCB1") (pin "P$23") (pinfunction "GPIO11_P$23") (pintype "bidirectional"))
    )
    (net (code "62") (name "unconnected-(PCB1-GPIO12-PadP$32)") (class "Default")
      (node (ref "PCB1") (pin "P$32") (pinfunction "GPIO12_P$32") (pintype "bidirectional"))
    )
    (net (code "63") (name "unconnected-(PCB1-GPIO13-PadP$33)") (class "Default")
      (node (ref "PCB1") (pin "P$33") (pinfunction "GPIO13_P$33") (pintype "bidirectional"))
    )
    (net (code "64") (name "unconnected-(PCB1-GPIO16-PadP$36)") (class "Default")
      (node (ref "PCB1") (pin "P$36") (pinfunction "GPIO16_P$36") (pintype "bidirectional"))
    )
    (net (code "65") (name "unconnected-(PCB1-GPIO17-PadP$11)") (class "Default")
      (node (ref "PCB1") (pin "P$11") (pinfunction "GPIO17_P$11") (pintype "bidirectional"))
    )
    (net (code "66") (name "unconnected-(PCB1-GPIO18-PadP$12)") (class "Default")
      (node (ref "PCB1") (pin "P$12") (pinfunction "GPIO18_P$12") (pintype "bidirectional"))
    )
    (net (code "67") (name "unconnected-(PCB1-GPIO19-PadP$35)") (class "Default")
      (node (ref "PCB1") (pin "P$35") (pinfunction "GPIO19_P$35") (pintype "bidirectional"))
    )
    (net (code "68") (name "unconnected-(PCB1-GPIO20-PadP$38)") (class "Default")
      (node (ref "PCB1") (pin "P$38") (pinfunction "GPIO20_P$38") (pintype "bidirectional"))
    )
    (net (code "69") (name "unconnected-(PCB1-GPIO21-PadP$40)") (class "Default")
      (node (ref "PCB1") (pin "P$40") (pinfunction "GPIO21_P$40") (pintype "bidirectional"))
    )
    (net (code "70") (name "unconnected-(PCB1-GPIO22-PadP$15)") (class "Default")
      (node (ref "PCB1") (pin "P$15") (pinfunction "GPIO22_P$15") (pintype "bidirectional"))
    )
    (net (code "71") (name "unconnected-(PCB1-GPIO23-PadP$16)") (class "Default")
      (node (ref "PCB1") (pin "P$16") (pinfunction "GPIO23_P$16") (pintype "bidirectional"))
    )
    (net (code "72") (name "unconnected-(PCB1-GPIO24-PadP$18)") (class "Default")
      (node (ref "PCB1") (pin "P$18") (pinfunction "GPIO24_P$18") (pintype "bidirectional"))
    )
    (net (code "73") (name "unconnected-(PCB1-GPIO25-PadP$22)") (class "Default")
      (node (ref "PCB1") (pin "P$22") (pinfunction "GPIO25_P$22") (pintype "bidirectional"))
    )
    (net (code "74") (name "unconnected-(PCB1-GPIO26-PadP$37)") (class "Default")
      (node (ref "PCB1") (pin "P$37") (pinfunction "GPIO26_P$37") (pintype "bidirectional"))
    )
    (net (code "75") (name "unconnected-(PCB1-GPIO27-PadP$13)") (class "Default")
      (node (ref "PCB1") (pin "P$13") (pinfunction "GPIO27_P$13") (pintype "bidirectional"))
    )
    (net (code "76") (name "unconnected-(PCB1-ID_SC*-PadP$28)") (class "Default")
      (node (ref "PCB1") (pin "P$28") (pinfunction "ID_SC*_P$28") (pintype "bidirectional"))
    )
    (net (code "77") (name "unconnected-(PCB1-ID_SD*-PadP$27)") (class "Default")
      (node (ref "PCB1") (pin "P$27") (pinfunction "ID_SD*_P$27") (pintype "bidirectional"))
    )
  )
)
